# led-driver.net
KiCad netlist of a schematic drawn in Altium Designer
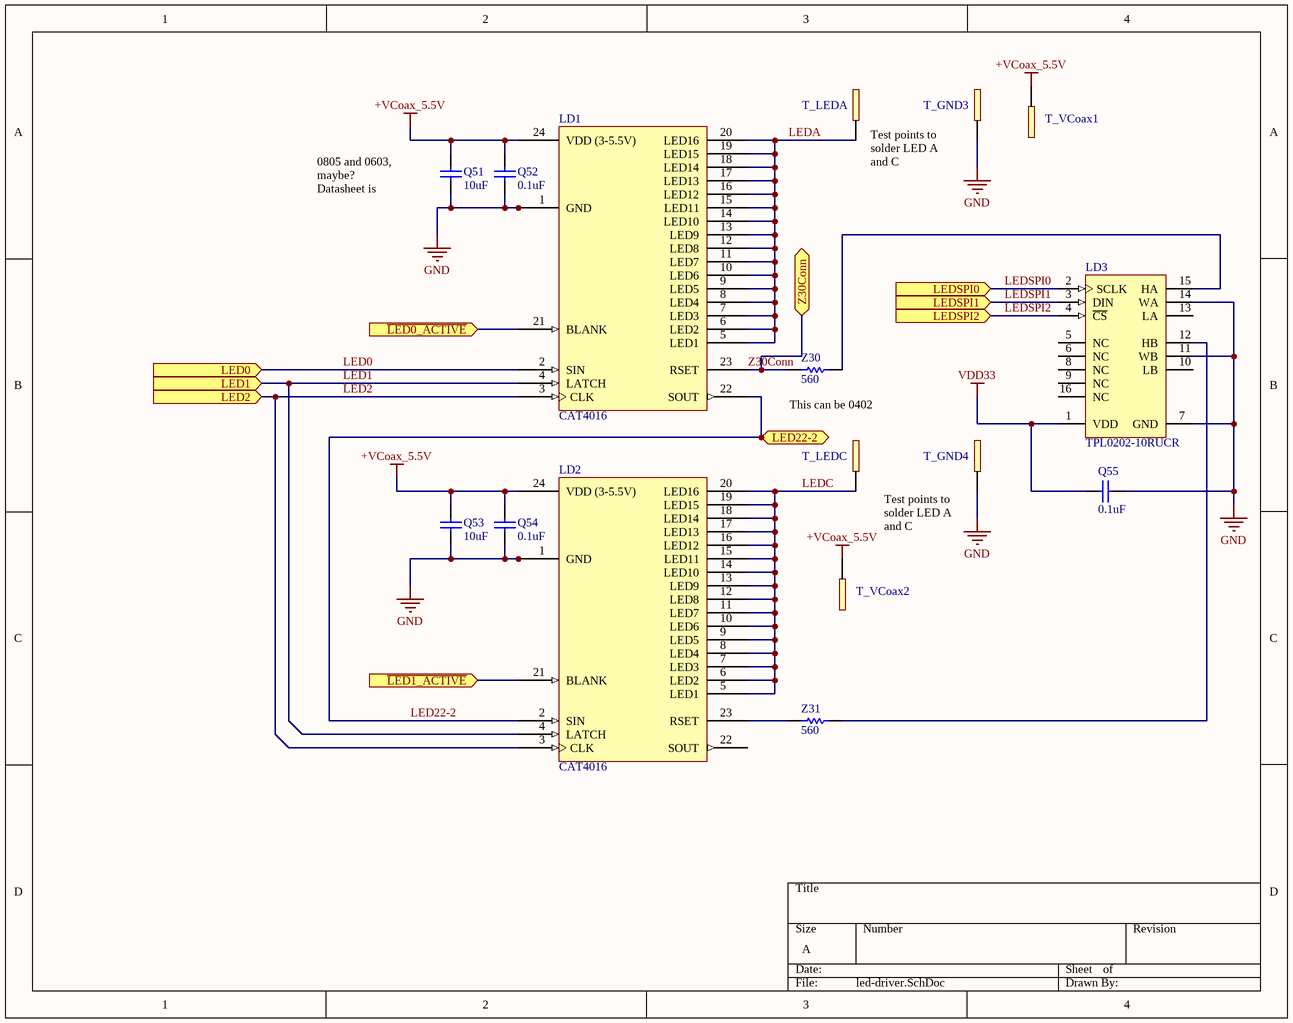
[diagram p0: led-driver.SchDoc]

(export (version "E")
  (design (tool "Eeschema 10.0.6"))
  (components
    (comp (ref "LD1")
      (value "CAT4016")
      (footprint "TQFN24-4x4mm")
      (description "16-Channel Constant Current LED Driver")
      (libsource (lib "jonnew") (part "CAT4016"))
    )
    (comp (ref "LD2")
      (value "CAT4016")
      (footprint "TQFN24-4x4mm")
      (description "16-Channel Constant Current LED Driver")
      (libsource (lib "jonnew") (part "CAT4016"))
    )
    (comp (ref "LD3")
      (value "TPL0202-10RUCR")
      (footprint "WQFN16-3X3mm")
      (fields (field (name "MANUFACTURER") "Texas Instruments"))
      (libsource (lib "jonnew") (part "TPL0202-10RUCR"))
    )
    (comp (ref "Q51")
      (value "10uF")
      (footprint "Cap-0603")
      (description "Capacitor")
      (fields (field (name "Comment") "Cap") (field (name "PUBLISHER") "Altium Limited"))
      (libsource (lib "Miscellaneous Devices") (part "Cap"))
    )
    (comp (ref "Q52")
      (value "0.1uF")
      (footprint "Cap_0402")
      (description "Capacitor")
      (fields (field (name "Comment") "Cap") (field (name "PUBLISHER") "Altium Limited"))
      (libsource (lib "Miscellaneous Devices") (part "Cap"))
    )
    (comp (ref "Q53")
      (value "10uF")
      (footprint "Cap-0603")
      (description "Capacitor")
      (fields (field (name "Comment") "Cap") (field (name "PUBLISHER") "Altium Limited"))
      (libsource (lib "Miscellaneous Devices") (part "Cap"))
    )
    (comp (ref "Q54")
      (value "0.1uF")
      (footprint "Cap_0402")
      (description "Capacitor")
      (fields (field (name "Comment") "Cap") (field (name "PUBLISHER") "Altium Limited"))
      (libsource (lib "Miscellaneous Devices") (part "Cap"))
    )
    (comp (ref "Q55")
      (value "0.1uF")
      (footprint "Cap_0402")
      (description "Capacitor")
      (fields (field (name "Comment") "Cap") (field (name "PUBLISHER") "Altium Limited"))
      (libsource (lib "Miscellaneous Devices") (part "Cap"))
    )
    (comp (ref "T_GND3")
      (value "Header_1PIN")
      (footprint "JUMPER1PIN")
      (libsource (lib "Jack_SCH_Lib1") (part "Header_1PIN"))
    )
    (comp (ref "T_GND4")
      (value "Header_1PIN")
      (footprint "JUMPER1PIN")
      (libsource (lib "Jack_SCH_Lib1") (part "Header_1PIN"))
    )
    (comp (ref "T_LEDA")
      (value "Header_1PIN")
      (footprint "JUMPER1PIN")
      (libsource (lib "Jack_SCH_Lib1") (part "Header_1PIN"))
    )
    (comp (ref "T_LEDC")
      (value "Header_1PIN")
      (footprint "JUMPER1PIN")
      (libsource (lib "Jack_SCH_Lib1") (part "Header_1PIN"))
    )
    (comp (ref "T_VCoax1")
      (value "Header_1PIN")
      (footprint "JUMPER1PIN")
      (libsource (lib "") (part "Header_1PIN_1"))
    )
    (comp (ref "T_VCoax2")
      (value "Header_1PIN")
      (footprint "JUMPER1PIN")
      (libsource (lib "") (part "Header_1PIN_1"))
    )
    (comp (ref "Z30")
      (value "560")
      (footprint "Res_0402")
      (description "Resistor")
      (fields (field (name "Comment") "Res1") (field (name "PUBLISHER") "Altium Limited"))
      (libsource (lib "Miscellaneous Devices") (part "Res1"))
    )
    (comp (ref "Z31")
      (value "560")
      (footprint "Res_0402")
      (description "Resistor")
      (fields (field (name "Comment") "Res1") (field (name "PUBLISHER") "Altium Limited"))
      (libsource (lib "Miscellaneous Devices") (part "Res1"))
    )
  )
  (nets
    (net (code "1") (name "+VCoax_5.5V") (class "Default")
      (node (ref "LD1") (pin "24") (pinfunction "VDD_(3-5.5V)_24") (pintype "power_in"))
      (node (ref "LD2") (pin "24") (pinfunction "VDD_(3-5.5V)_24") (pintype "power_in"))
      (node (ref "Q51") (pin "2") (pinfunction "2_2") (pintype "passive"))
      (node (ref "Q52") (pin "2") (pinfunction "2_2") (pintype "passive"))
      (node (ref "Q53") (pin "2") (pinfunction "2_2") (pintype "passive"))
      (node (ref "Q54") (pin "2") (pinfunction "2_2") (pintype "passive"))
      (node (ref "T_VCoax1") (pin "0") (pinfunction "0_0") (pintype "passive"))
      (node (ref "T_VCoax2") (pin "0") (pinfunction "0_0") (pintype "passive"))
    )
    (net (code "2") (name "/LED0") (class "Default")
      (node (ref "LD1") (pin "2") (pinfunction "SIN_2") (pintype "input"))
    )
    (net (code "3") (name "/LED1") (class "Default")
      (node (ref "LD1") (pin "4") (pinfunction "LATCH_4") (pintype "input"))
      (node (ref "LD2") (pin "4") (pinfunction "LATCH_4") (pintype "input"))
    )
    (net (code "4") (name "/LED2") (class "Default")
      (node (ref "LD1") (pin "3") (pinfunction "CLK_3") (pintype "input"))
      (node (ref "LD2") (pin "3") (pinfunction "CLK_3") (pintype "input"))
    )
    (net (code "5") (name "/LED22-2") (class "Default")
      (node (ref "LD1") (pin "22") (pinfunction "SOUT_22") (pintype "output"))
      (node (ref "LD2") (pin "2") (pinfunction "SIN_2") (pintype "input"))
    )
    (net (code "6") (name "/LEDA") (class "Default")
      (node (ref "LD1") (pin "10") (pinfunction "LED6_10") (pintype "passive"))
      (node (ref "LD1") (pin "11") (pinfunction "LED7_11") (pintype "passive"))
      (node (ref "LD1") (pin "12") (pinfunction "LED8_12") (pintype "passive"))
      (node (ref "LD1") (pin "13") (pinfunction "LED9_13") (pintype "passive"))
      (node (ref "LD1") (pin "14") (pinfunction "LED10_14") (pintype "passive"))
      (node (ref "LD1") (pin "15") (pinfunction "LED11_15") (pintype "passive"))
      (node (ref "LD1") (pin "16") (pinfunction "LED12_16") (pintype "passive"))
      (node (ref "LD1") (pin "17") (pinfunction "LED13_17") (pintype "passive"))
      (node (ref "LD1") (pin "18") (pinfunction "LED14_18") (pintype "passive"))
      (node (ref "LD1") (pin "19") (pinfunction "LED15_19") (pintype "passive"))
      (node (ref "LD1") (pin "20") (pinfunction "LED16_20") (pintype "passive"))
      (node (ref "LD1") (pin "5") (pinfunction "LED1_5") (pintype "passive"))
      (node (ref "LD1") (pin "6") (pinfunction "LED2_6") (pintype "passive"))
      (node (ref "LD1") (pin "7") (pinfunction "LED3_7") (pintype "passive"))
      (node (ref "LD1") (pin "8") (pinfunction "LED4_8") (pintype "passive"))
      (node (ref "LD1") (pin "9") (pinfunction "LED5_9") (pintype "passive"))
      (node (ref "T_LEDA") (pin "0") (pinfunction "0_0") (pintype "passive"))
    )
    (net (code "7") (name "/LEDC") (class "Default")
      (node (ref "LD2") (pin "10") (pinfunction "LED6_10") (pintype "passive"))
      (node (ref "LD2") (pin "11") (pinfunction "LED7_11") (pintype "passive"))
      (node (ref "LD2") (pin "12") (pinfunction "LED8_12") (pintype "passive"))
      (node (ref "LD2") (pin "13") (pinfunction "LED9_13") (pintype "passive"))
      (node (ref "LD2") (pin "14") (pinfunction "LED10_14") (pintype "passive"))
      (node (ref "LD2") (pin "15") (pinfunction "LED11_15") (pintype "passive"))
      (node (ref "LD2") (pin "16") (pinfunction "LED12_16") (pintype "passive"))
      (node (ref "LD2") (pin "17") (pinfunction "LED13_17") (pintype "passive"))
      (node (ref "LD2") (pin "18") (pinfunction "LED14_18") (pintype "passive"))
      (node (ref "LD2") (pin "19") (pinfunction "LED15_19") (pintype "passive"))
      (node (ref "LD2") (pin "20") (pinfunction "LED16_20") (pintype "passive"))
      (node (ref "LD2") (pin "5") (pinfunction "LED1_5") (pintype "passive"))
      (node (ref "LD2") (pin "6") (pinfunction "LED2_6") (pintype "passive"))
      (node (ref "LD2") (pin "7") (pinfunction "LED3_7") (pintype "passive"))
      (node (ref "LD2") (pin "8") (pinfunction "LED4_8") (pintype "passive"))
      (node (ref "LD2") (pin "9") (pinfunction "LED5_9") (pintype "passive"))
      (node (ref "T_LEDC") (pin "0") (pinfunction "0_0") (pintype "passive"))
    )
    (net (code "8") (name "/LEDSPI0") (class "Default")
      (node (ref "LD3") (pin "2") (pinfunction "SCLK_2") (pintype "input"))
    )
    (net (code "9") (name "/LEDSPI1") (class "Default")
      (node (ref "LD3") (pin "3") (pinfunction "DIN_3") (pintype "input"))
    )
    (net (code "10") (name "/LEDSPI2") (class "Default")
      (node (ref "LD3") (pin "4") (pinfunction "~{CS}_4") (pintype "input"))
    )
    (net (code "11") (name "/Z30Conn") (class "Default")
      (node (ref "LD1") (pin "23") (pinfunction "RSET_23") (pintype "passive"))
      (node (ref "Z30") (pin "2") (pinfunction "2_2") (pintype "passive"))
    )
    (net (code "12") (name "/~{LED0_ACTIVE}") (class "Default")
      (node (ref "LD1") (pin "21") (pinfunction "BLANK_21") (pintype "input"))
    )
    (net (code "13") (name "/~{LED1_ACTIVE}") (class "Default")
      (node (ref "LD2") (pin "21") (pinfunction "BLANK_21") (pintype "input"))
    )
    (net (code "14") (name "GND") (class "Default")
      (node (ref "LD1") (pin "1") (pinfunction "GND_1") (pintype "power_in"))
      (node (ref "LD1") (pin "PAD") (pintype "power_in"))
      (node (ref "LD2") (pin "1") (pinfunction "GND_1") (pintype "power_in"))
      (node (ref "LD2") (pin "PAD") (pintype "power_in"))
      (node (ref "LD3") (pin "11") (pinfunction "WB_11") (pintype "passive"))
      (node (ref "LD3") (pin "14") (pinfunction "WA_14") (pintype "passive"))
      (node (ref "LD3") (pin "7") (pinfunction "GND_7") (pintype "power_in"))
      (node (ref "Q51") (pin "1") (pinfunction "1_1") (pintype "passive"))
      (node (ref "Q52") (pin "1") (pinfunction "1_1") (pintype "passive"))
      (node (ref "Q53") (pin "1") (pinfunction "1_1") (pintype "passive"))
      (node (ref "Q54") (pin "1") (pinfunction "1_1") (pintype "passive"))
      (node (ref "Q55") (pin "2") (pinfunction "2_2") (pintype "passive"))
      (node (ref "T_GND3") (pin "0") (pinfunction "0_0") (pintype "passive"))
      (node (ref "T_GND4") (pin "0") (pinfunction "0_0") (pintype "passive"))
    )
    (net (code "15") (name "Net-(LD2-RSET)") (class "Default")
      (node (ref "LD2") (pin "23") (pinfunction "RSET_23") (pintype "passive"))
      (node (ref "Z31") (pin "2") (pinfunction "2_2") (pintype "passive"))
    )
    (net (code "16") (name "Net-(LD3-HA)") (class "Default")
      (node (ref "LD3") (pin "15") (pinfunction "HA_15") (pintype "passive"))
      (node (ref "Z30") (pin "1") (pinfunction "1_1") (pintype "passive"))
    )
    (net (code "17") (name "Net-(LD3-HB)") (class "Default")
      (node (ref "LD3") (pin "12") (pinfunction "HB_12") (pintype "passive"))
      (node (ref "Z31") (pin "1") (pinfunction "1_1") (pintype "passive"))
    )
    (net (code "18") (name "VDD33") (class "Default")
      (node (ref "LD3") (pin "1") (pinfunction "VDD_1") (pintype "power_in"))
      (node (ref "Q55") (pin "1") (pinfunction "1_1") (pintype "passive"))
    )
    (net (code "19") (name "unconnected-(LD2-SOUT-Pad22)") (class "Default")
      (node (ref "LD2") (pin "22") (pinfunction "SOUT_22") (pintype "output"))
    )
    (net (code "20") (name "unconnected-(LD3-LA-Pad13)") (class "Default")
      (node (ref "LD3") (pin "13") (pinfunction "LA_13") (pintype "passive"))
    )
    (net (code "21") (name "unconnected-(LD3-LB-Pad10)") (class "Default")
      (node (ref "LD3") (pin "10") (pinfunction "LB_10") (pintype "passive"))
    )
    (net (code "22") (name "unconnected-(LD3-NC-Pad5)") (class "Default")
      (node (ref "LD3") (pin "5") (pinfunction "NC_5") (pintype "passive"))
    )
    (net (code "23") (name "unconnected-(LD3-NC-Pad6)") (class "Default")
      (node (ref "LD3") (pin "6") (pinfunction "NC_6") (pintype "passive"))
    )
    (net (code "24") (name "unconnected-(LD3-NC-Pad8)") (class "Default")
      (node (ref "LD3") (pin "8") (pinfunction "NC_8") (pintype "passive"))
    )
    (net (code "25") (name "unconnected-(LD3-NC-Pad9)") (class "Default")
      (node (ref "LD3") (pin "9") (pinfunction "NC_9") (pintype "passive"))
    )
    (net (code "26") (name "unconnected-(LD3-NC-Pad16)") (class "Default")
      (node (ref "LD3") (pin "16") (pinfunction "NC_16") (pintype "passive"))
    )
  )
)
